# RES_2_0_transmitter.net
KiCad netlist of a schematic drawn in Altium Designer
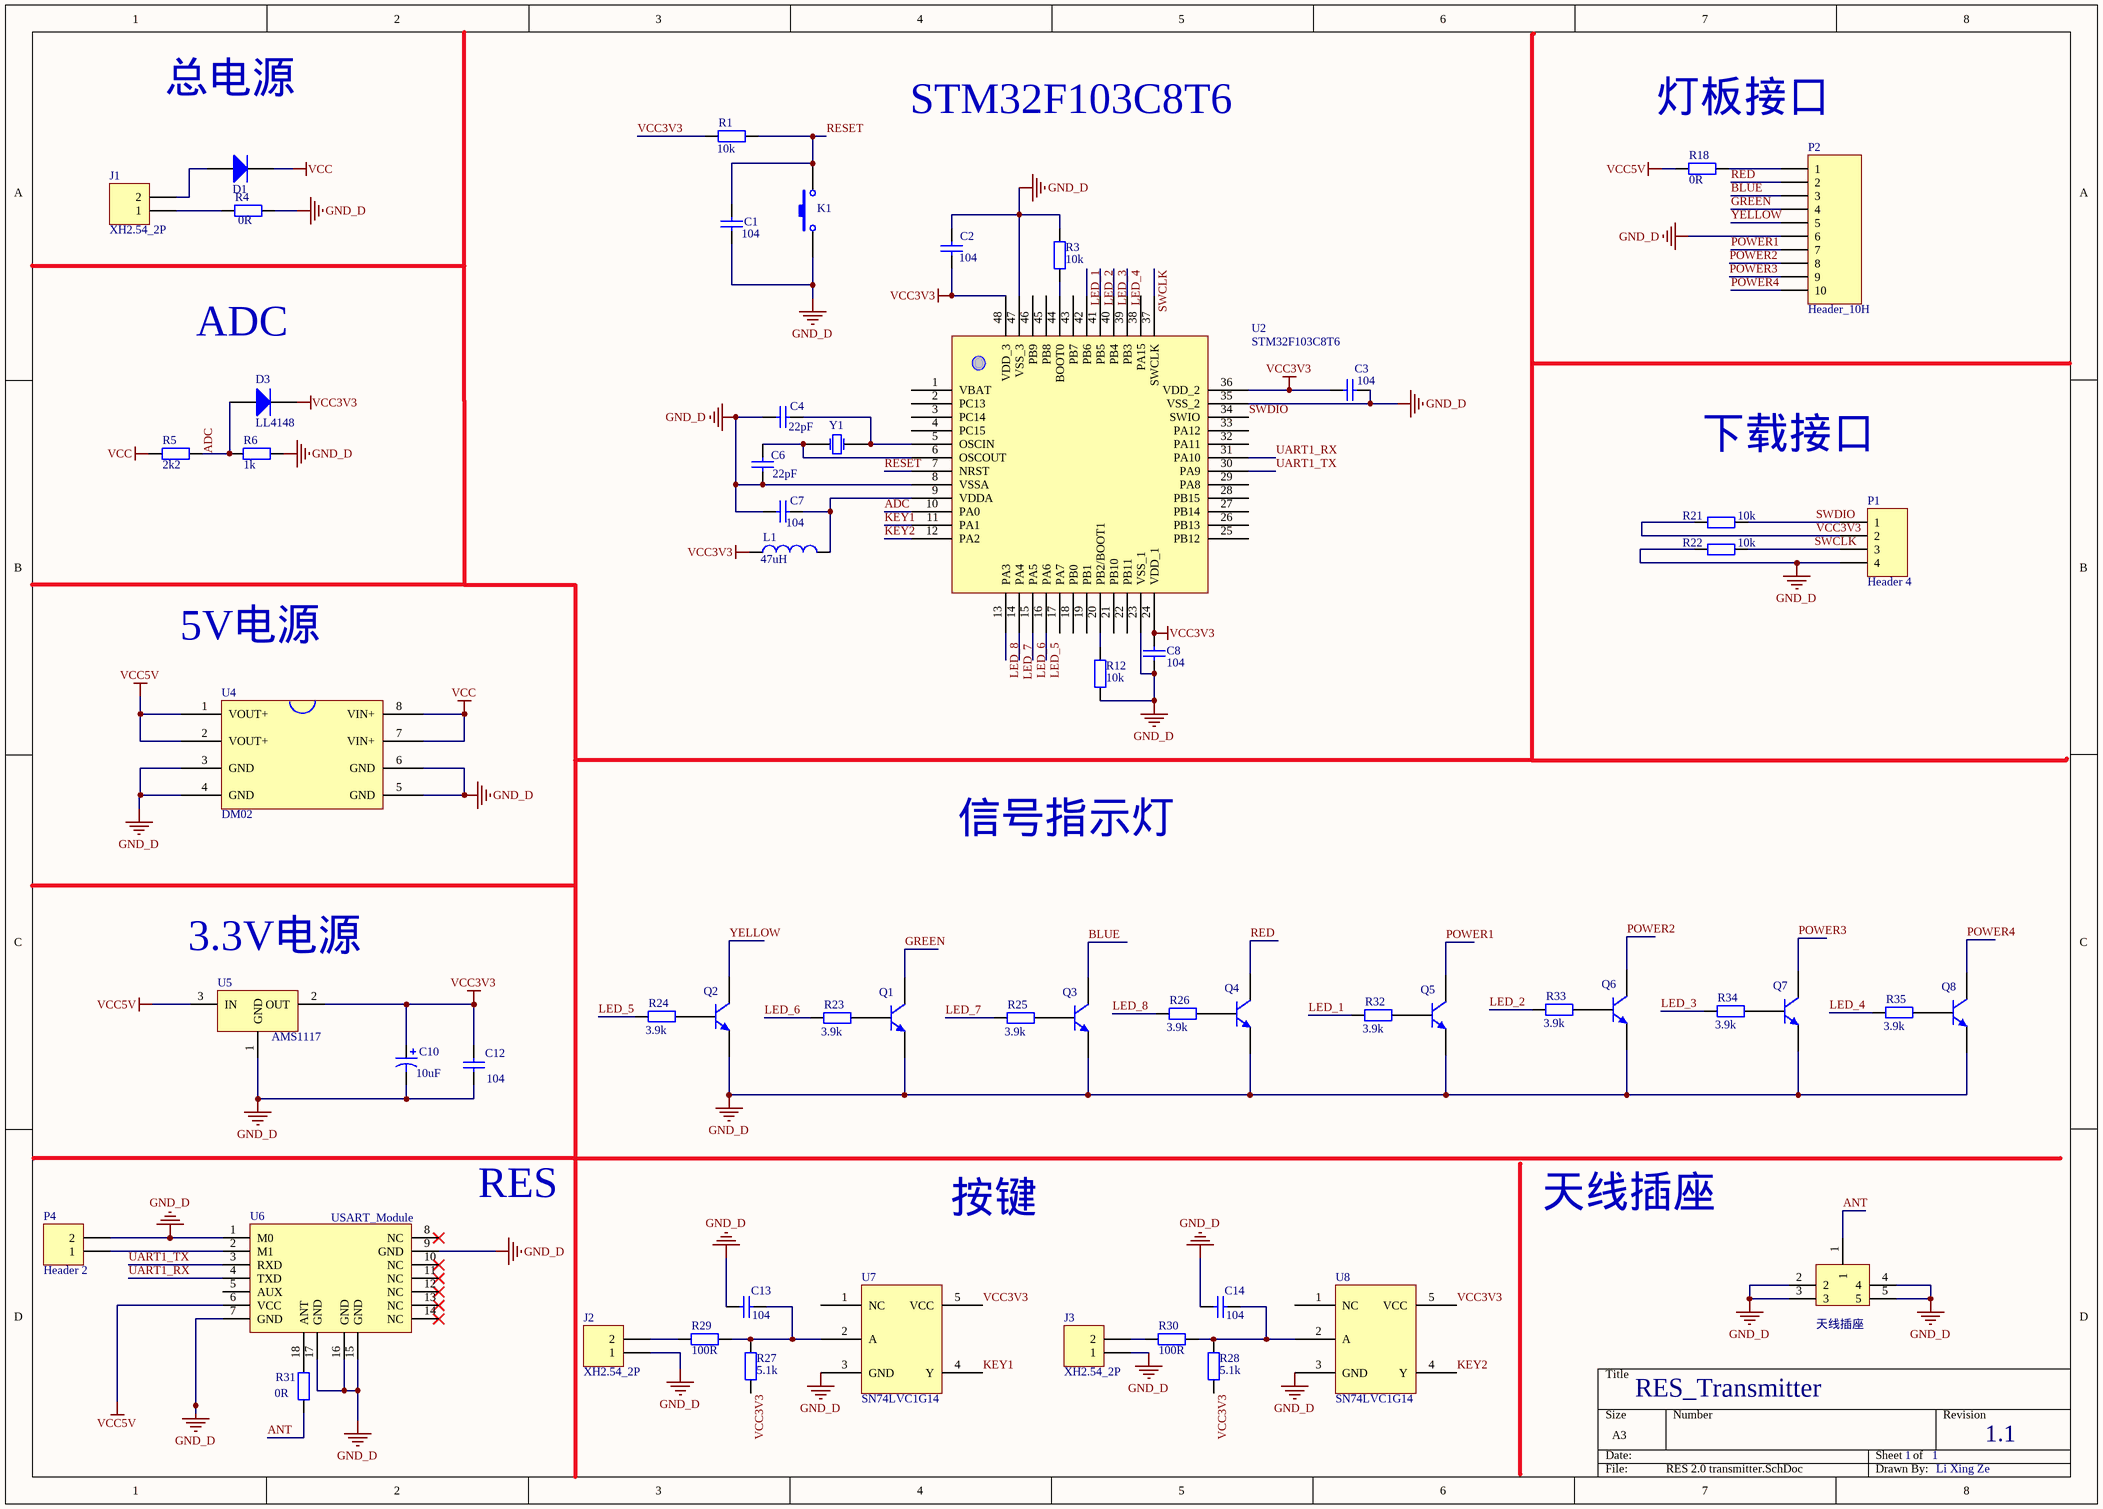
[diagram p0: RES 2.0 transmitter.SchDoc]

(export (version "E")
  (design (tool "Eeschema 10.0.6"))
  (components
    (comp (ref "C1")
      (value "104")
      (footprint "C 0805")
      (description "无极性电容")
      (fields (field (name "Comment") "Cap vol"))
      (libsource (lib "HRT_D Integrated_Library") (part "Cap"))
    )
    (comp (ref "C2")
      (value "104")
      (footprint "C 0805")
      (description "无极性电容")
      (fields (field (name "Comment") "Cap vol"))
      (libsource (lib "HRT_D Integrated_Library") (part "Cap"))
    )
    (comp (ref "C3")
      (value "104")
      (footprint "C 0805")
      (description "无极性电容")
      (fields (field (name "Comment") "Cap vol"))
      (libsource (lib "HRT_D Integrated_Library") (part "Cap"))
    )
    (comp (ref "C4")
      (value "22pF")
      (footprint "C 0805")
      (description "无极性电容")
      (fields (field (name "Comment") "Cap vol"))
      (libsource (lib "HRT_D Integrated_Library") (part "Cap"))
    )
    (comp (ref "C6")
      (value "22pF")
      (footprint "C 0805")
      (description "无极性电容")
      (fields (field (name "Comment") "Cap vol"))
      (libsource (lib "HRT_D Integrated_Library") (part "Cap"))
    )
    (comp (ref "C7")
      (value "104")
      (footprint "C 0805")
      (description "无极性电容")
      (fields (field (name "Comment") "Cap vol"))
      (libsource (lib "HRT_D Integrated_Library") (part "Cap"))
    )
    (comp (ref "C8")
      (value "104")
      (footprint "C 0805")
      (description "无极性电容")
      (fields (field (name "Comment") "Cap vol"))
      (libsource (lib "HRT_D Integrated_Library") (part "Cap"))
    )
    (comp (ref "C10")
      (value "10uF")
      (footprint "CP 3528B")
      (description "极性电容")
      (fields (field (name "Comment") "Cap vol"))
      (libsource (lib "HRT_D Integrated_Library") (part "Cap_Pol"))
    )
    (comp (ref "C12")
      (value "104")
      (footprint "C 0805")
      (description "无极性电容")
      (fields (field (name "Comment") "Cap vol"))
      (libsource (lib "HRT_D Integrated_Library") (part "Cap"))
    )
    (comp (ref "C13")
      (value "104")
      (footprint "C 0805")
      (description "无极性电容")
      (fields (field (name "Comment") "Cap vol"))
      (libsource (lib "HRT_D Integrated_Library") (part "Cap"))
    )
    (comp (ref "C14")
      (value "104")
      (footprint "C 0805")
      (description "无极性电容")
      (fields (field (name "Comment") "Cap vol"))
      (libsource (lib "HRT_D Integrated_Library") (part "Cap"))
    )
    (comp (ref "D1")
      (value "SS14")
      (footprint "DO-214")
      (description "肖特基（快恢复）二极管")
      (libsource (lib "HRT_D Integrated_Library") (part "Diode"))
    )
    (comp (ref "D3")
      (value "LL4148")
      (footprint "LL34")
      (description "开关二极管")
      (libsource (lib "HRT_D Integrated_Library") (part "Diode"))
    )
    (comp (ref "J1")
      (value "XH2.54_2P")
      (footprint "XH2.54_2P_SMT")
      (description "XH2.54Header,2-pin")
      (libsource (lib "HRT_D Integrated_Library") (part "XH2.54_2P"))
    )
    (comp (ref "J2")
      (value "XH2.54_2P")
      (footprint "XH2.54_2P_SMT")
      (libsource (lib "HRT_D Integrated_Library") (part "XH2.54_2P"))
    )
    (comp (ref "J3")
      (value "XH2.54_2P")
      (footprint "XH2.54_2P_SMT")
      (libsource (lib "HRT_D Integrated_Library") (part "XH2.54_2P"))
    )
    (comp (ref "K1")
      (value "Key")
      (footprint "KEY 3.6*2.5 SMD")
      (description "按键")
      (libsource (lib "HRT_D Integrated_Library") (part "Key"))
    )
    (comp (ref "L1")
      (value "47uH")
      (footprint "L 0805")
      (description "电感")
      (fields (field (name "Comment") "Inductor"))
      (libsource (lib "HRT_D Integrated_Library") (part "Inductor"))
    )
    (comp (ref "P1")
      (value "Header 4")
      (footprint "HDR1X4")
      (description "Header, 4-Pin")
      (fields (field (name "PUBLISHER") "Altium Limited"))
      (libsource (lib "Miscellaneous Connectors") (part "Header 4"))
    )
    (comp (ref "P2")
      (value "Header_10H")
      (footprint "Header_10H")
      (libsource (lib "HRT_D Schlib") (part "Header_10H"))
    )
    (comp (ref "P3") (value "天线插座") (footprint "ANT") (libsource (lib "HRT_D Schlib") (part "天线插座")))
    (comp (ref "P4")
      (value "Header 2")
      (footprint "HDR1X2")
      (description "Header, 2-Pin")
      (fields (field (name "PUBLISHER") "Altium Limited"))
      (libsource (lib "Miscellaneous Connectors") (part "Header 2"))
    )
    (comp (ref "Q1")
      (value "Model")
      (footprint "SOT23-3")
      (description "NPN三极管")
      (libsource (lib "HRT_D Integrated_Library") (part "Transistor_NPN"))
    )
    (comp (ref "Q2")
      (value "Model")
      (footprint "SOT23-3")
      (description "NPN三极管")
      (libsource (lib "HRT_D Integrated_Library") (part "Transistor_NPN"))
    )
    (comp (ref "Q3")
      (value "Model")
      (footprint "SOT23-3")
      (description "NPN三极管")
      (libsource (lib "HRT_D Integrated_Library") (part "Transistor_NPN"))
    )
    (comp (ref "Q4")
      (value "Model")
      (footprint "SOT23-3")
      (description "NPN三极管")
      (libsource (lib "HRT_D Integrated_Library") (part "Transistor_NPN"))
    )
    (comp (ref "Q5")
      (value "Model")
      (footprint "SOT23-3")
      (description "NPN三极管")
      (libsource (lib "HRT_D Integrated_Library") (part "Transistor_NPN"))
    )
    (comp (ref "Q6")
      (value "Model")
      (footprint "SOT23-3")
      (description "NPN三极管")
      (libsource (lib "HRT_D Integrated_Library") (part "Transistor_NPN"))
    )
    (comp (ref "Q7")
      (value "Model")
      (footprint "SOT23-3")
      (description "NPN三极管")
      (libsource (lib "HRT_D Integrated_Library") (part "Transistor_NPN"))
    )
    (comp (ref "Q8")
      (value "Model")
      (footprint "SOT23-3")
      (description "NPN三极管")
      (libsource (lib "HRT_D Integrated_Library") (part "Transistor_NPN"))
    )
    (comp (ref "R1")
      (value "10k")
      (footprint "R 0805")
      (description "电阻")
      (fields (field (name "Comment") "Res"))
      (libsource (lib "HRT_D Integrated_Library") (part "Resistor"))
    )
    (comp (ref "R3")
      (value "10k")
      (footprint "R 0805")
      (description "电阻")
      (fields (field (name "Comment") "Res"))
      (libsource (lib "") (part "Resistor_1"))
    )
    (comp (ref "R4")
      (value "0R")
      (footprint "R 1206")
      (description "电阻")
      (fields (field (name "Comment") "Res"))
      (libsource (lib "") (part "Resistor_2"))
    )
    (comp (ref "R5")
      (value "2k2")
      (footprint "R 0805")
      (description "电阻")
      (fields (field (name "Comment") "Res"))
      (libsource (lib "HRT_D Integrated_Library") (part "Resistor"))
    )
    (comp (ref "R6")
      (value "1k")
      (footprint "R 0805")
      (description "电阻")
      (fields (field (name "Comment") "Res"))
      (libsource (lib "HRT_D Integrated_Library") (part "Resistor"))
    )
    (comp (ref "R12")
      (value "10k")
      (footprint "R 0805")
      (description "电阻")
      (fields (field (name "Comment") "Res"))
      (libsource (lib "") (part "Resistor_1"))
    )
    (comp (ref "R18")
      (value "0R")
      (footprint "R 0805")
      (description "电阻")
      (fields (field (name "Comment") "Res"))
      (libsource (lib "HRT_D Integrated_Library") (part "Resistor"))
    )
    (comp (ref "R21")
      (value "10k")
      (footprint "R 0805")
      (description "电阻")
      (fields (field (name "Comment") "Res"))
      (libsource (lib "HRT_D Integrated_Library") (part "Resistor"))
    )
    (comp (ref "R22")
      (value "10k")
      (footprint "R 0805")
      (description "电阻")
      (fields (field (name "Comment") "Res"))
      (libsource (lib "HRT_D Integrated_Library") (part "Resistor"))
    )
    (comp (ref "R23")
      (value "3.9k")
      (footprint "R 0805")
      (description "电阻")
      (fields (field (name "Comment") "Res"))
      (libsource (lib "HRT_D Integrated_Library") (part "Resistor"))
    )
    (comp (ref "R24")
      (value "3.9k")
      (footprint "R 0805")
      (description "电阻")
      (fields (field (name "Comment") "Res"))
      (libsource (lib "HRT_D Integrated_Library") (part "Resistor"))
    )
    (comp (ref "R25")
      (value "3.9k")
      (footprint "R 0805")
      (description "电阻")
      (fields (field (name "Comment") "Res"))
      (libsource (lib "HRT_D Integrated_Library") (part "Resistor"))
    )
    (comp (ref "R26")
      (value "3.9k")
      (footprint "R 0805")
      (description "电阻")
      (fields (field (name "Comment") "Res"))
      (libsource (lib "HRT_D Integrated_Library") (part "Resistor"))
    )
    (comp (ref "R27")
      (value "5.1k")
      (footprint "R 0805")
      (description "电阻")
      (fields (field (name "Comment") "Res"))
      (libsource (lib "") (part "Resistor_1"))
    )
    (comp (ref "R28")
      (value "5.1k")
      (footprint "R 0805")
      (description "电阻")
      (fields (field (name "Comment") "Res"))
      (libsource (lib "") (part "Resistor_1"))
    )
    (comp (ref "R29")
      (value "100R")
      (footprint "R 0805")
      (description "电阻")
      (fields (field (name "Comment") "Res"))
      (libsource (lib "HRT_D Integrated_Library") (part "Resistor"))
    )
    (comp (ref "R30")
      (value "100R")
      (footprint "R 0805")
      (description "电阻")
      (fields (field (name "Comment") "Res"))
      (libsource (lib "HRT_D Integrated_Library") (part "Resistor"))
    )
    (comp (ref "R31")
      (value "0R")
      (footprint "R 0805")
      (description "Resistor")
      (fields (field (name "Comment") "Res2") (field (name "PUBLISHER") "Altium Limited"))
      (libsource (lib "Miscellaneous Devices") (part "Res2"))
    )
    (comp (ref "R32")
      (value "3.9k")
      (footprint "R 0805")
      (description "电阻")
      (fields (field (name "Comment") "Res"))
      (libsource (lib "HRT_D Integrated_Library") (part "Resistor"))
    )
    (comp (ref "R33")
      (value "3.9k")
      (footprint "R 0805")
      (description "电阻")
      (fields (field (name "Comment") "Res"))
      (libsource (lib "HRT_D Integrated_Library") (part "Resistor"))
    )
    (comp (ref "R34")
      (value "3.9k")
      (footprint "R 0805")
      (description "电阻")
      (fields (field (name "Comment") "Res"))
      (libsource (lib "HRT_D Integrated_Library") (part "Resistor"))
    )
    (comp (ref "R35")
      (value "3.9k")
      (footprint "R 0805")
      (description "电阻")
      (fields (field (name "Comment") "Res"))
      (libsource (lib "HRT_D Integrated_Library") (part "Resistor"))
    )
    (comp (ref "U2")
      (value "STM32F103C8T6")
      (footprint "LQFP48")
      (description "Micro controller")
      (libsource (lib "HRT_D Integrated_Library") (part "STM32F103C8T6"))
    )
    (comp (ref "U4")
      (value "DM02")
      (footprint "DM02")
      (description "开关型DC-DC变换器")
      (libsource (lib "HRT_D Integrated_Library") (part "DM02"))
    )
    (comp (ref "U5")
      (value "AMS1117")
      (footprint "SOT223")
      (description "线性稳压器")
      (libsource (lib "HRT_D Integrated_Library") (part "AMS1117"))
    )
    (comp (ref "U6") (value "USART_Module") (footprint "USART_Module") (libsource (lib "RES") (part "RES")))
    (comp (ref "U7")
      (value "SN74LVC1G14")
      (footprint "SOT23-5")
      (description "单路施密特反相器")
      (libsource (lib "HRT_D Integrated_Library") (part "SN74LVC1G14"))
    )
    (comp (ref "U8")
      (value "SN74LVC1G14")
      (footprint "SOT23-5")
      (description "单路施密特反相器")
      (libsource (lib "HRT_D Integrated_Library") (part "SN74LVC1G14"))
    )
    (comp (ref "Y1")
      (value "Freq")
      (footprint "XTAL-5032")
      (description "晶振")
      (libsource (lib "HRT_D Integrated_Library") (part "XTAL"))
    )
  )
  (nets
    (net (code "1") (name "/ADC") (class "Default")
      (node (ref "D3") (pin "1") (pinfunction "A_1") (pintype "passive"))
      (node (ref "R5") (pin "1") (pinfunction "1_1") (pintype "passive"))
      (node (ref "R6") (pin "2") (pinfunction "2_2") (pintype "passive"))
      (node (ref "U2") (pin "10") (pinfunction "PA0_10") (pintype "passive"))
    )
    (net (code "2") (name "/ANT") (class "Default")
      (node (ref "P3") (pin "1") (pinfunction "1_1") (pintype "passive"))
      (node (ref "R31") (pin "1") (pinfunction "1_1") (pintype "passive"))
    )
    (net (code "3") (name "/BLUE") (class "Default")
      (node (ref "P2") (pin "3") (pinfunction "3_3") (pintype "passive"))
      (node (ref "Q3") (pin "3") (pinfunction "C_3") (pintype "passive"))
    )
    (net (code "4") (name "/GREEN") (class "Default")
      (node (ref "P2") (pin "4") (pinfunction "4_4") (pintype "passive"))
      (node (ref "Q1") (pin "3") (pinfunction "C_3") (pintype "passive"))
    )
    (net (code "5") (name "/KEY1") (class "Default")
      (node (ref "U2") (pin "11") (pinfunction "PA1_11") (pintype "passive"))
      (node (ref "U7") (pin "4") (pinfunction "Y_4") (pintype "passive"))
    )
    (net (code "6") (name "/KEY2") (class "Default")
      (node (ref "U2") (pin "12") (pinfunction "PA2_12") (pintype "passive"))
      (node (ref "U8") (pin "4") (pinfunction "Y_4") (pintype "passive"))
    )
    (net (code "7") (name "/LED_1") (class "Default")
      (node (ref "R32") (pin "2") (pinfunction "2_2") (pintype "passive"))
      (node (ref "U2") (pin "42") (pinfunction "PB6_42") (pintype "passive"))
    )
    (net (code "8") (name "/LED_2") (class "Default")
      (node (ref "R33") (pin "2") (pinfunction "2_2") (pintype "passive"))
      (node (ref "U2") (pin "41") (pinfunction "PB5_41") (pintype "passive"))
    )
    (net (code "9") (name "/LED_3") (class "Default")
      (node (ref "R34") (pin "2") (pinfunction "2_2") (pintype "passive"))
      (node (ref "U2") (pin "40") (pinfunction "PB4_40") (pintype "passive"))
    )
    (net (code "10") (name "/LED_4") (class "Default")
      (node (ref "R35") (pin "2") (pinfunction "2_2") (pintype "passive"))
      (node (ref "U2") (pin "39") (pinfunction "PB3_39") (pintype "passive"))
    )
    (net (code "11") (name "/LED_5") (class "Default")
      (node (ref "R24") (pin "2") (pinfunction "2_2") (pintype "passive"))
      (node (ref "U2") (pin "16") (pinfunction "PA6_16") (pintype "passive"))
    )
    (net (code "12") (name "/LED_6") (class "Default")
      (node (ref "R23") (pin "2") (pinfunction "2_2") (pintype "passive"))
      (node (ref "U2") (pin "15") (pinfunction "PA5_15") (pintype "passive"))
    )
    (net (code "13") (name "/LED_7") (class "Default")
      (node (ref "R25") (pin "2") (pinfunction "2_2") (pintype "passive"))
      (node (ref "U2") (pin "14") (pinfunction "PA4_14") (pintype "passive"))
    )
    (net (code "14") (name "/LED_8") (class "Default")
      (node (ref "R26") (pin "2") (pinfunction "2_2") (pintype "passive"))
      (node (ref "U2") (pin "13") (pinfunction "PA3_13") (pintype "passive"))
    )
    (net (code "15") (name "/POWER1") (class "Default")
      (node (ref "P2") (pin "7") (pinfunction "7_7") (pintype "passive"))
      (node (ref "Q5") (pin "3") (pinfunction "C_3") (pintype "passive"))
    )
    (net (code "16") (name "/POWER2") (class "Default")
      (node (ref "P2") (pin "8") (pinfunction "8_8") (pintype "passive"))
      (node (ref "Q6") (pin "3") (pinfunction "C_3") (pintype "passive"))
    )
    (net (code "17") (name "/POWER3") (class "Default")
      (node (ref "P2") (pin "9") (pinfunction "9_9") (pintype "passive"))
      (node (ref "Q7") (pin "3") (pinfunction "C_3") (pintype "passive"))
    )
    (net (code "18") (name "/POWER4") (class "Default")
      (node (ref "P2") (pin "10") (pinfunction "10_10") (pintype "passive"))
      (node (ref "Q8") (pin "3") (pinfunction "C_3") (pintype "passive"))
    )
    (net (code "19") (name "/RED") (class "Default")
      (node (ref "P2") (pin "2") (pinfunction "2_2") (pintype "passive"))
      (node (ref "Q4") (pin "3") (pinfunction "C_3") (pintype "passive"))
    )
    (net (code "20") (name "/RESET") (class "Default")
      (node (ref "C1") (pin "2") (pinfunction "2_2") (pintype "passive"))
      (node (ref "K1") (pin "2") (pinfunction "2_2") (pintype "passive"))
      (node (ref "R1") (pin "1") (pinfunction "1_1") (pintype "passive"))
      (node (ref "U2") (pin "7") (pinfunction "NRST_7") (pintype "passive"))
    )
    (net (code "21") (name "/SWCLK") (class "Default")
      (node (ref "P1") (pin "3") (pinfunction "3_3") (pintype "passive"))
      (node (ref "R22") (pin "1") (pinfunction "1_1") (pintype "passive"))
      (node (ref "U2") (pin "37") (pinfunction "SWCLK_37") (pintype "passive"))
    )
    (net (code "22") (name "/SWDIO") (class "Default")
      (node (ref "P1") (pin "1") (pinfunction "1_1") (pintype "passive"))
      (node (ref "R21") (pin "1") (pinfunction "1_1") (pintype "passive"))
      (node (ref "U2") (pin "34") (pinfunction "SWIO_34") (pintype "passive"))
    )
    (net (code "23") (name "/UART1_RX") (class "Default")
      (node (ref "U2") (pin "31") (pinfunction "PA10_31") (pintype "passive"))
      (node (ref "U6") (pin "4") (pinfunction "TXD_4") (pintype "passive"))
    )
    (net (code "24") (name "/UART1_TX") (class "Default")
      (node (ref "U2") (pin "30") (pinfunction "PA9_30") (pintype "passive"))
      (node (ref "U6") (pin "3") (pinfunction "RXD_3") (pintype "passive"))
    )
    (net (code "25") (name "/YELLOW") (class "Default")
      (node (ref "P2") (pin "5") (pinfunction "5_5") (pintype "passive"))
      (node (ref "Q2") (pin "3") (pinfunction "C_3") (pintype "passive"))
    )
    (net (code "26") (name "GND_D") (class "Default")
      (node (ref "C1") (pin "1") (pinfunction "1_1") (pintype "passive"))
      (node (ref "C10") (pin "2") (pinfunction "2_2") (pintype "passive"))
      (node (ref "C12") (pin "1") (pinfunction "1_1") (pintype "passive"))
      (node (ref "C13") (pin "1") (pinfunction "1_1") (pintype "passive"))
      (node (ref "C14") (pin "1") (pinfunction "1_1") (pintype "passive"))
      (node (ref "C2") (pin "2") (pinfunction "2_2") (pintype "passive"))
      (node (ref "C3") (pin "2") (pinfunction "2_2") (pintype "passive"))
      (node (ref "C4") (pin "1") (pinfunction "1_1") (pintype "passive"))
      (node (ref "C6") (pin "1") (pinfunction "1_1") (pintype "passive"))
      (node (ref "C7") (pin "1") (pinfunction "1_1") (pintype "passive"))
      (node (ref "C8") (pin "1") (pinfunction "1_1") (pintype "passive"))
      (node (ref "J2") (pin "1") (pinfunction "1_1") (pintype "passive"))
      (node (ref "J3") (pin "1") (pinfunction "1_1") (pintype "passive"))
      (node (ref "K1") (pin "1") (pinfunction "1_1") (pintype "passive"))
      (node (ref "P1") (pin "4") (pinfunction "4_4") (pintype "passive"))
      (node (ref "P2") (pin "6") (pinfunction "6_6") (pintype "passive"))
      (node (ref "P3") (pin "2") (pinfunction "2_2") (pintype "passive"))
      (node (ref "P3") (pin "3") (pinfunction "3_3") (pintype "passive"))
      (node (ref "P3") (pin "4") (pinfunction "4_4") (pintype "passive"))
      (node (ref "P3") (pin "5") (pinfunction "5_5") (pintype "passive"))
      (node (ref "P4") (pin "2") (pinfunction "2_2") (pintype "passive"))
      (node (ref "Q1") (pin "2") (pinfunction "E_2") (pintype "passive"))
      (node (ref "Q2") (pin "2") (pinfunction "E_2") (pintype "passive"))
      (node (ref "Q3") (pin "2") (pinfunction "E_2") (pintype "passive"))
      (node (ref "Q4") (pin "2") (pinfunction "E_2") (pintype "passive"))
      (node (ref "Q5") (pin "2") (pinfunction "E_2") (pintype "passive"))
      (node (ref "Q6") (pin "2") (pinfunction "E_2") (pintype "passive"))
      (node (ref "Q7") (pin "2") (pinfunction "E_2") (pintype "passive"))
      (node (ref "Q8") (pin "2") (pinfunction "E_2") (pintype "passive"))
      (node (ref "R12") (pin "1") (pinfunction "1_1") (pintype "passive"))
      (node (ref "R22") (pin "2") (pinfunction "2_2") (pintype "passive"))
      (node (ref "R3") (pin "2") (pinfunction "2_2") (pintype "passive"))
      (node (ref "R4") (pin "2") (pinfunction "2_2") (pintype "passive"))
      (node (ref "R6") (pin "1") (pinfunction "1_1") (pintype "passive"))
      (node (ref "U2") (pin "23") (pinfunction "VSS_1_23") (pintype "passive"))
      (node (ref "U2") (pin "35") (pinfunction "VSS_2_35") (pintype "passive"))
      (node (ref "U2") (pin "47") (pinfunction "VSS_3_47") (pintype "passive"))
      (node (ref "U2") (pin "8") (pinfunction "VSSA_8") (pintype "passive"))
      (node (ref "U4") (pin "3") (pinfunction "GND_3") (pintype "passive"))
      (node (ref "U4") (pin "4") (pinfunction "GND_4") (pintype "passive"))
      (node (ref "U4") (pin "5") (pinfunction "GND_5") (pintype "passive"))
      (node (ref "U4") (pin "6") (pinfunction "GND_6") (pintype "passive"))
      (node (ref "U5") (pin "1") (pinfunction "GND_1") (pintype "power_in"))
      (node (ref "U6") (pin "1") (pinfunction "M0_1") (pintype "passive"))
      (node (ref "U6") (pin "15") (pinfunction "GND_15") (pintype "passive"))
      (node (ref "U6") (pin "16") (pinfunction "GND_16") (pintype "passive"))
      (node (ref "U6") (pin "17") (pinfunction "GND_17") (pintype "passive"))
      (node (ref "U6") (pin "7") (pinfunction "GND_7") (pintype "passive"))
      (node (ref "U6") (pin "9") (pinfunction "GND_9") (pintype "passive"))
      (node (ref "U7") (pin "3") (pinfunction "GND_3") (pintype "passive"))
      (node (ref "U8") (pin "3") (pinfunction "GND_3") (pintype "passive"))
    )
    (net (code "27") (name "Net-(D1-A)") (class "Default")
      (node (ref "D1") (pin "1") (pinfunction "A_1") (pintype "passive"))
      (node (ref "J1") (pin "2") (pinfunction "2_2") (pintype "passive"))
    )
    (net (code "28") (name "Net-(J1-Pad1)") (class "Default")
      (node (ref "J1") (pin "1") (pinfunction "1_1") (pintype "passive"))
      (node (ref "R4") (pin "1") (pinfunction "1_1") (pintype "passive"))
    )
    (net (code "29") (name "Net-(J2-Pad2)") (class "Default")
      (node (ref "J2") (pin "2") (pinfunction "2_2") (pintype "passive"))
      (node (ref "R29") (pin "2") (pinfunction "2_2") (pintype "passive"))
    )
    (net (code "30") (name "Net-(J3-Pad2)") (class "Default")
      (node (ref "J3") (pin "2") (pinfunction "2_2") (pintype "passive"))
      (node (ref "R30") (pin "2") (pinfunction "2_2") (pintype "passive"))
    )
    (net (code "31") (name "Net-(P2-Pad1)") (class "Default")
      (node (ref "P2") (pin "1") (pinfunction "1_1") (pintype "passive"))
      (node (ref "R18") (pin "1") (pinfunction "1_1") (pintype "passive"))
    )
    (net (code "32") (name "Net-(Q1-B)") (class "Default")
      (node (ref "Q1") (pin "1") (pinfunction "B_1") (pintype "passive"))
      (node (ref "R23") (pin "1") (pinfunction "1_1") (pintype "passive"))
    )
    (net (code "33") (name "Net-(Q2-B)") (class "Default")
      (node (ref "Q2") (pin "1") (pinfunction "B_1") (pintype "passive"))
      (node (ref "R24") (pin "1") (pinfunction "1_1") (pintype "passive"))
    )
    (net (code "34") (name "Net-(Q3-B)") (class "Default")
      (node (ref "Q3") (pin "1") (pinfunction "B_1") (pintype "passive"))
      (node (ref "R25") (pin "1") (pinfunction "1_1") (pintype "passive"))
    )
    (net (code "35") (name "Net-(Q4-B)") (class "Default")
      (node (ref "Q4") (pin "1") (pinfunction "B_1") (pintype "passive"))
      (node (ref "R26") (pin "1") (pinfunction "1_1") (pintype "passive"))
    )
    (net (code "36") (name "Net-(Q5-B)") (class "Default")
      (node (ref "Q5") (pin "1") (pinfunction "B_1") (pintype "passive"))
      (node (ref "R32") (pin "1") (pinfunction "1_1") (pintype "passive"))
    )
    (net (code "37") (name "Net-(Q6-B)") (class "Default")
      (node (ref "Q6") (pin "1") (pinfunction "B_1") (pintype "passive"))
      (node (ref "R33") (pin "1") (pinfunction "1_1") (pintype "passive"))
    )
    (net (code "38") (name "Net-(Q7-B)") (class "Default")
      (node (ref "Q7") (pin "1") (pinfunction "B_1") (pintype "passive"))
      (node (ref "R34") (pin "1") (pinfunction "1_1") (pintype "passive"))
    )
    (net (code "39") (name "Net-(Q8-B)") (class "Default")
      (node (ref "Q8") (pin "1") (pinfunction "B_1") (pintype "passive"))
      (node (ref "R35") (pin "1") (pinfunction "1_1") (pintype "passive"))
    )
    (net (code "40") (name "Net-(U2-BOOT0)") (class "Default")
      (node (ref "R3") (pin "1") (pinfunction "1_1") (pintype "passive"))
      (node (ref "U2") (pin "44") (pinfunction "BOOT0_44") (pintype "passive"))
    )
    (net (code "41") (name "Net-(U2-OSCIN)") (class "Default")
      (node (ref "C4") (pin "2") (pinfunction "2_2") (pintype "passive"))
      (node (ref "U2") (pin "5") (pinfunction "OSCIN_5") (pintype "passive"))
      (node (ref "Y1") (pin "2") (pinfunction "OSC2_2") (pintype "passive"))
    )
    (net (code "42") (name "Net-(U2-OSCOUT)") (class "Default")
      (node (ref "C6") (pin "2") (pinfunction "2_2") (pintype "passive"))
      (node (ref "U2") (pin "6") (pinfunction "OSCOUT_6") (pintype "passive"))
      (node (ref "Y1") (pin "1") (pinfunction "OSC1_1") (pintype "passive"))
    )
    (net (code "43") (name "Net-(U2-PB2{slash}BOOT1)") (class "Default")
      (node (ref "R12") (pin "2") (pinfunction "2_2") (pintype "passive"))
      (node (ref "U2") (pin "20") (pinfunction "PB2/BOOT1_20") (pintype "passive"))
    )
    (net (code "44") (name "Net-(U2-VDDA)") (class "Default")
      (node (ref "C7") (pin "2") (pinfunction "2_2") (pintype "passive"))
      (node (ref "L1") (pin "2") (pinfunction "2_2") (pintype "passive"))
      (node (ref "U2") (pin "9") (pinfunction "VDDA_9") (pintype "passive"))
    )
    (net (code "45") (name "Net-(U6-ANT)") (class "Default")
      (node (ref "R31") (pin "2") (pinfunction "2_2") (pintype "passive"))
      (node (ref "U6") (pin "18") (pinfunction "ANT_18") (pintype "passive"))
    )
    (net (code "46") (name "Net-(U6-M1)") (class "Default")
      (node (ref "P4") (pin "1") (pinfunction "1_1") (pintype "passive"))
      (node (ref "U6") (pin "2") (pinfunction "M1_2") (pintype "passive"))
    )
    (net (code "47") (name "Net-(U7-A)") (class "Default")
      (node (ref "C13") (pin "2") (pinfunction "2_2") (pintype "passive"))
      (node (ref "R27") (pin "2") (pinfunction "2_2") (pintype "passive"))
      (node (ref "R29") (pin "1") (pinfunction "1_1") (pintype "passive"))
      (node (ref "U7") (pin "2") (pinfunction "A_2") (pintype "passive"))
    )
    (net (code "48") (name "Net-(U8-A)") (class "Default")
      (node (ref "C14") (pin "2") (pinfunction "2_2") (pintype "passive"))
      (node (ref "R28") (pin "2") (pinfunction "2_2") (pintype "passive"))
      (node (ref "R30") (pin "1") (pinfunction "1_1") (pintype "passive"))
      (node (ref "U8") (pin "2") (pinfunction "A_2") (pintype "passive"))
    )
    (net (code "49") (name "VCC") (class "Default")
      (node (ref "D1") (pin "2") (pinfunction "K_2") (pintype "passive"))
      (node (ref "R5") (pin "2") (pinfunction "2_2") (pintype "passive"))
      (node (ref "U4") (pin "7") (pinfunction "VIN+_7") (pintype "passive"))
      (node (ref "U4") (pin "8") (pinfunction "VIN+_8") (pintype "passive"))
    )
    (net (code "50") (name "VCC3V3") (class "Default")
      (node (ref "C10") (pin "1") (pinfunction "1_1") (pintype "passive"))
      (node (ref "C12") (pin "2") (pinfunction "2_2") (pintype "passive"))
      (node (ref "C2") (pin "1") (pinfunction "1_1") (pintype "passive"))
      (node (ref "C3") (pin "1") (pinfunction "1_1") (pintype "passive"))
      (node (ref "C8") (pin "2") (pinfunction "2_2") (pintype "passive"))
      (node (ref "D3") (pin "2") (pinfunction "K_2") (pintype "passive"))
      (node (ref "L1") (pin "1") (pinfunction "1_1") (pintype "passive"))
      (node (ref "P1") (pin "2") (pinfunction "2_2") (pintype "passive"))
      (node (ref "R1") (pin "2") (pinfunction "2_2") (pintype "passive"))
      (node (ref "R21") (pin "2") (pinfunction "2_2") (pintype "passive"))
      (node (ref "R27") (pin "1") (pinfunction "1_1") (pintype "passive"))
      (node (ref "R28") (pin "1") (pinfunction "1_1") (pintype "passive"))
      (node (ref "U2") (pin "24") (pinfunction "VDD_1_24") (pintype "passive"))
      (node (ref "U2") (pin "36") (pinfunction "VDD_2_36") (pintype "passive"))
      (node (ref "U2") (pin "48") (pinfunction "VDD_3_48") (pintype "passive"))
      (node (ref "U5") (pin "2") (pinfunction "OUT_2") (pintype "power_in"))
      (node (ref "U7") (pin "5") (pinfunction "VCC_5") (pintype "passive"))
      (node (ref "U8") (pin "5") (pinfunction "VCC_5") (pintype "passive"))
    )
    (net (code "51") (name "VCC5V") (class "Default")
      (node (ref "R18") (pin "2") (pinfunction "2_2") (pintype "passive"))
      (node (ref "U4") (pin "1") (pinfunction "VOUT+_1") (pintype "passive"))
      (node (ref "U4") (pin "2") (pinfunction "VOUT+_2") (pintype "passive"))
      (node (ref "U5") (pin "3") (pinfunction "IN_3") (pintype "power_in"))
      (node (ref "U6") (pin "6") (pinfunction "VCC_6") (pintype "passive"))
    )
    (net (code "52") (name "unconnected-(U2-PA7-Pad17)") (class "Default")
      (node (ref "U2") (pin "17") (pinfunction "PA7_17") (pintype "passive"))
    )
    (net (code "53") (name "unconnected-(U2-PA8-Pad29)") (class "Default")
      (node (ref "U2") (pin "29") (pinfunction "PA8_29") (pintype "passive"))
    )
    (net (code "54") (name "unconnected-(U2-PA11-Pad32)") (class "Default")
      (node (ref "U2") (pin "32") (pinfunction "PA11_32") (pintype "passive"))
    )
    (net (code "55") (name "unconnected-(U2-PA12-Pad33)") (class "Default")
      (node (ref "U2") (pin "33") (pinfunction "PA12_33") (pintype "passive"))
    )
    (net (code "56") (name "unconnected-(U2-PA15-Pad38)") (class "Default")
      (node (ref "U2") (pin "38") (pinfunction "PA15_38") (pintype "passive"))
    )
    (net (code "57") (name "unconnected-(U2-PB0-Pad18)") (class "Default")
      (node (ref "U2") (pin "18") (pinfunction "PB0_18") (pintype "passive"))
    )
    (net (code "58") (name "unconnected-(U2-PB1-Pad19)") (class "Default")
      (node (ref "U2") (pin "19") (pinfunction "PB1_19") (pintype "passive"))
    )
    (net (code "59") (name "unconnected-(U2-PB7-Pad43)") (class "Default")
      (node (ref "U2") (pin "43") (pinfunction "PB7_43") (pintype "passive"))
    )
    (net (code "60") (name "unconnected-(U2-PB8-Pad45)") (class "Default")
      (node (ref "U2") (pin "45") (pinfunction "PB8_45") (pintype "passive"))
    )
    (net (code "61") (name "unconnected-(U2-PB9-Pad46)") (class "Default")
      (node (ref "U2") (pin "46") (pinfunction "PB9_46") (pintype "passive"))
    )
    (net (code "62") (name "unconnected-(U2-PB10-Pad21)") (class "Default")
      (node (ref "U2") (pin "21") (pinfunction "PB10_21") (pintype "passive"))
    )
    (net (code "63") (name "unconnected-(U2-PB11-Pad22)") (class "Default")
      (node (ref "U2") (pin "22") (pinfunction "PB11_22") (pintype "passive"))
    )
    (net (code "64") (name "unconnected-(U2-PB12-Pad25)") (class "Default")
      (node (ref "U2") (pin "25") (pinfunction "PB12_25") (pintype "passive"))
    )
    (net (code "65") (name "unconnected-(U2-PB13-Pad26)") (class "Default")
      (node (ref "U2") (pin "26") (pinfunction "PB13_26") (pintype "passive"))
    )
    (net (code "66") (name "unconnected-(U2-PB14-Pad27)") (class "Default")
      (node (ref "U2") (pin "27") (pinfunction "PB14_27") (pintype "passive"))
    )
    (net (code "67") (name "unconnected-(U2-PB15-Pad28)") (class "Default")
      (node (ref "U2") (pin "28") (pinfunction "PB15_28") (pintype "passive"))
    )
    (net (code "68") (name "unconnected-(U2-PC13-Pad2)") (class "Default")
      (node (ref "U2") (pin "2") (pinfunction "PC13_2") (pintype "passive"))
    )
    (net (code "69") (name "unconnected-(U2-PC14-Pad3)") (class "Default")
      (node (ref "U2") (pin "3") (pinfunction "PC14_3") (pintype "passive"))
    )
    (net (code "70") (name "unconnected-(U2-PC15-Pad4)") (class "Default")
      (node (ref "U2") (pin "4") (pinfunction "PC15_4") (pintype "passive"))
    )
    (net (code "71") (name "unconnected-(U2-VBAT-Pad1)") (class "Default")
      (node (ref "U2") (pin "1") (pinfunction "VBAT_1") (pintype "passive"))
    )
    (net (code "72") (name "unconnected-(U6-AUX-Pad5)") (class "Default")
      (node (ref "U6") (pin "5") (pinfunction "AUX_5") (pintype "passive"))
    )
    (net (code "73") (name "unconnected-(U6-NC-Pad8)") (class "Default")
      (node (ref "U6") (pin "8") (pinfunction "NC_8") (pintype "passive+no_connect"))
    )
    (net (code "74") (name "unconnected-(U6-NC-Pad10)") (class "Default")
      (node (ref "U6") (pin "10") (pinfunction "NC_10") (pintype "passive+no_connect"))
    )
    (net (code "75") (name "unconnected-(U6-NC-Pad11)") (class "Default")
      (node (ref "U6") (pin "11") (pinfunction "NC_11") (pintype "passive+no_connect"))
    )
    (net (code "76") (name "unconnected-(U6-NC-Pad12)") (class "Default")
      (node (ref "U6") (pin "12") (pinfunction "NC_12") (pintype "passive+no_connect"))
    )
    (net (code "77") (name "unconnected-(U6-NC-Pad13)") (class "Default")
      (node (ref "U6") (pin "13") (pinfunction "NC_13") (pintype "passive+no_connect"))
    )
    (net (code "78") (name "unconnected-(U6-NC-Pad14)") (class "Default")
      (node (ref "U6") (pin "14") (pinfunction "NC_14") (pintype "passive+no_connect"))
    )
    (net (code "79") (name "unconnected-(U7-NC-Pad1)") (class "Default")
      (node (ref "U7") (pin "1") (pinfunction "NC_1") (pintype "passive"))
    )
    (net (code "80") (name "unconnected-(U8-NC-Pad1)") (class "Default")
      (node (ref "U8") (pin "1") (pinfunction "NC_1") (pintype "passive"))
    )
  )
)
